# LED1710050926.net
KiCad netlist of a schematic drawn in Altium Designer
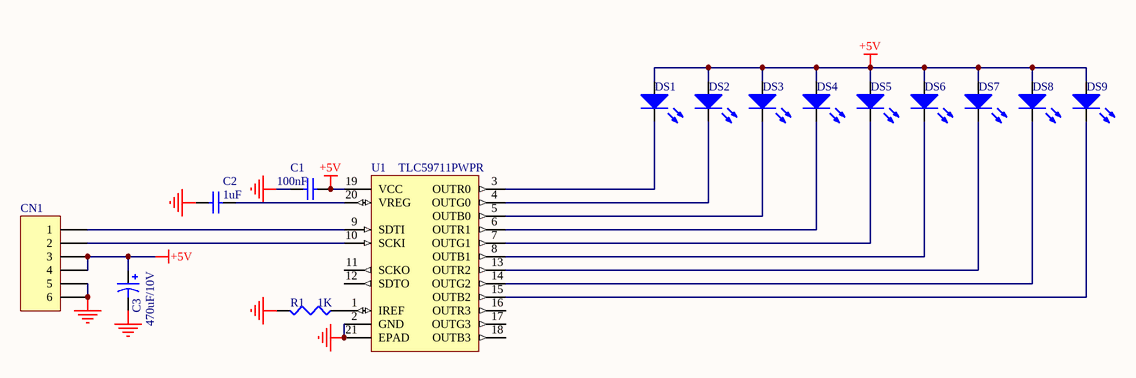
[diagram p0: LED1710050926.SchDoc]

(export (version "E")
  (design (tool "Eeschema 10.0.6"))
  (components
    (comp (ref "C1")
      (value "100nF")
      (footprint "C0603-3")
      (description "Capacitor")
      (fields (field (name "PUBLISHER") "Altium Limited"))
      (libsource (lib "Miscellaneous Devices") (part "Cap"))
    )
    (comp (ref "C2")
      (value "1uF")
      (footprint "C0603-3")
      (description "Capacitor")
      (fields (field (name "PUBLISHER") "Altium Limited"))
      (libsource (lib "Miscellaneous Devices") (part "Cap"))
    )
    (comp (ref "C3")
      (value "470uF/10V")
      (footprint "CASE-D_7343")
      (description "Polarized Capacitor (Radial)")
      (fields (field (name "PUBLISHER") "Altium Limited"))
      (libsource (lib "Miscellaneous Devices") (part "Cap Pol1"))
    )
    (comp (ref "CN1")
      (value "~")
      (footprint "FFC/SM1.0-2H6")
      (description "Header, 6-Pin")
      (fields (field (name "PUBLISHER") "Altium Limited"))
      (libsource (lib "Miscellaneous Connectors") (part "Header 6"))
    )
    (comp (ref "DS1")
      (value "~")
      (footprint "LED2-2.54-5C")
      (description "Typical INFRARED GaAs LED")
      (fields (field (name "PUBLISHER") "Altium Limited"))
      (libsource (lib "Sch1609122025") (part "LED0"))
    )
    (comp (ref "DS2")
      (value "~")
      (footprint "LED2-2.54-5C")
      (description "Typical INFRARED GaAs LED")
      (fields (field (name "PUBLISHER") "Altium Limited"))
      (libsource (lib "Sch1609122025") (part "LED0"))
    )
    (comp (ref "DS3")
      (value "~")
      (footprint "LED2-2.54-5C")
      (description "Typical INFRARED GaAs LED")
      (fields (field (name "PUBLISHER") "Altium Limited"))
      (libsource (lib "Sch1609122025") (part "LED0"))
    )
    (comp (ref "DS4")
      (value "~")
      (footprint "LED2-2.54-5C")
      (description "Typical INFRARED GaAs LED")
      (fields (field (name "PUBLISHER") "Altium Limited"))
      (libsource (lib "Sch1609122025") (part "LED0"))
    )
    (comp (ref "DS5")
      (value "~")
      (footprint "LED2-2.54-5C")
      (description "Typical INFRARED GaAs LED")
      (fields (field (name "PUBLISHER") "Altium Limited"))
      (libsource (lib "Sch1609122025") (part "LED0"))
    )
    (comp (ref "DS6")
      (value "~")
      (footprint "LED2-2.54-5C")
      (description "Typical INFRARED GaAs LED")
      (fields (field (name "PUBLISHER") "Altium Limited"))
      (libsource (lib "Sch1609122025") (part "LED0"))
    )
    (comp (ref "DS7")
      (value "~")
      (footprint "LED2-2.54-5C")
      (description "Typical INFRARED GaAs LED")
      (fields (field (name "PUBLISHER") "Altium Limited"))
      (libsource (lib "Sch1609122025") (part "LED0"))
    )
    (comp (ref "DS8")
      (value "~")
      (footprint "LED2-2.54-5C")
      (description "Typical INFRARED GaAs LED")
      (fields (field (name "PUBLISHER") "Altium Limited"))
      (libsource (lib "Sch1609122025") (part "LED0"))
    )
    (comp (ref "DS9")
      (value "~")
      (footprint "LED2-2.54-5C")
      (description "Typical INFRARED GaAs LED")
      (fields (field (name "PUBLISHER") "Altium Limited"))
      (libsource (lib "Sch1609122025") (part "LED0"))
    )
    (comp (ref "R1")
      (value "1K")
      (footprint "R0603-3")
      (description "Resistor")
      (fields (field (name "PUBLISHER") "Altium Limited"))
      (libsource (lib "Miscellaneous Devices") (part "Res3"))
    )
    (comp (ref "U1")
      (value "TLC59711PWPR")
      (footprint "HTSSOP20")
      (description "12-Channel,16-Bit,LED Driver with 3.3-V Linear Ragulator")
      (libsource (lib "Sch1705181056") (part "TLC59711"))
    )
  )
  (nets
    (net (code "1") (name "+5V") (class "Default")
      (node (ref "C1") (pin "1") (pinfunction "1_1") (pintype "passive"))
      (node (ref "C3") (pin "1") (pinfunction "1_1") (pintype "passive"))
      (node (ref "CN1") (pin "3") (pinfunction "3_3") (pintype "passive"))
      (node (ref "CN1") (pin "4") (pinfunction "4_4") (pintype "passive"))
      (node (ref "DS1") (pin "1") (pinfunction "A_1") (pintype "passive"))
      (node (ref "DS2") (pin "1") (pinfunction "A_1") (pintype "passive"))
      (node (ref "DS3") (pin "1") (pinfunction "A_1") (pintype "passive"))
      (node (ref "DS4") (pin "1") (pinfunction "A_1") (pintype "passive"))
      (node (ref "DS5") (pin "1") (pinfunction "A_1") (pintype "passive"))
      (node (ref "DS6") (pin "1") (pinfunction "A_1") (pintype "passive"))
      (node (ref "DS7") (pin "1") (pinfunction "A_1") (pintype "passive"))
      (node (ref "DS8") (pin "1") (pinfunction "A_1") (pintype "passive"))
      (node (ref "DS9") (pin "1") (pinfunction "A_1") (pintype "passive"))
      (node (ref "U1") (pin "19") (pinfunction "VCC_19") (pintype "power_in"))
    )
    (net (code "2") (name "GND") (class "Default")
      (node (ref "C1") (pin "2") (pinfunction "2_2") (pintype "passive"))
      (node (ref "C2") (pin "2") (pinfunction "2_2") (pintype "passive"))
      (node (ref "C3") (pin "2") (pinfunction "2_2") (pintype "passive"))
      (node (ref "CN1") (pin "5") (pinfunction "5_5") (pintype "passive"))
      (node (ref "CN1") (pin "6") (pinfunction "6_6") (pintype "passive"))
      (node (ref "R1") (pin "2") (pinfunction "2_2") (pintype "passive"))
      (node (ref "U1") (pin "2") (pinfunction "GND_2") (pintype "power_in"))
      (node (ref "U1") (pin "21") (pinfunction "EPAD_21") (pintype "passive"))
    )
    (net (code "3") (name "Net-(DS1-K)") (class "Default")
      (node (ref "DS1") (pin "2") (pinfunction "K_2") (pintype "passive"))
      (node (ref "U1") (pin "3") (pinfunction "OUTR0_3") (pintype "output"))
    )
    (net (code "4") (name "Net-(DS2-K)") (class "Default")
      (node (ref "DS2") (pin "2") (pinfunction "K_2") (pintype "passive"))
      (node (ref "U1") (pin "4") (pinfunction "OUTG0_4") (pintype "output"))
    )
    (net (code "5") (name "Net-(DS3-K)") (class "Default")
      (node (ref "DS3") (pin "2") (pinfunction "K_2") (pintype "passive"))
      (node (ref "U1") (pin "5") (pinfunction "OUTB0_5") (pintype "output"))
    )
    (net (code "6") (name "Net-(DS4-K)") (class "Default")
      (node (ref "DS4") (pin "2") (pinfunction "K_2") (pintype "passive"))
      (node (ref "U1") (pin "6") (pinfunction "OUTR1_6") (pintype "output"))
    )
    (net (code "7") (name "Net-(DS5-K)") (class "Default")
      (node (ref "DS5") (pin "2") (pinfunction "K_2") (pintype "passive"))
      (node (ref "U1") (pin "7") (pinfunction "OUTG1_7") (pintype "output"))
    )
    (net (code "8") (name "Net-(DS6-K)") (class "Default")
      (node (ref "DS6") (pin "2") (pinfunction "K_2") (pintype "passive"))
      (node (ref "U1") (pin "8") (pinfunction "OUTB1_8") (pintype "output"))
    )
    (net (code "9") (name "Net-(DS7-K)") (class "Default")
      (node (ref "DS7") (pin "2") (pinfunction "K_2") (pintype "passive"))
      (node (ref "U1") (pin "13") (pinfunction "OUTR2_13") (pintype "output"))
    )
    (net (code "10") (name "Net-(DS8-K)") (class "Default")
      (node (ref "DS8") (pin "2") (pinfunction "K_2") (pintype "passive"))
      (node (ref "U1") (pin "14") (pinfunction "OUTG2_14") (pintype "output"))
    )
    (net (code "11") (name "Net-(DS9-K)") (class "Default")
      (node (ref "DS9") (pin "2") (pinfunction "K_2") (pintype "passive"))
      (node (ref "U1") (pin "15") (pinfunction "OUTB2_15") (pintype "output"))
    )
    (net (code "12") (name "Net-(U1-IREF)") (class "Default")
      (node (ref "R1") (pin "1") (pinfunction "1_1") (pintype "passive"))
      (node (ref "U1") (pin "1") (pinfunction "IREF_1") (pintype "bidirectional"))
    )
    (net (code "13") (name "Net-(U1-SCKI)") (class "Default")
      (node (ref "CN1") (pin "2") (pinfunction "2_2") (pintype "passive"))
      (node (ref "U1") (pin "10") (pinfunction "SCKI_10") (pintype "input"))
    )
    (net (code "14") (name "Net-(U1-SDTI)") (class "Default")
      (node (ref "CN1") (pin "1") (pinfunction "1_1") (pintype "passive"))
      (node (ref "U1") (pin "9") (pinfunction "SDTI_9") (pintype "input"))
    )
    (net (code "15") (name "Net-(U1-VREG)") (class "Default")
      (node (ref "C2") (pin "1") (pinfunction "1_1") (pintype "passive"))
      (node (ref "U1") (pin "20") (pinfunction "VREG_20") (pintype "bidirectional"))
    )
    (net (code "16") (name "unconnected-(U1-OUTB3-Pad18)") (class "Default")
      (node (ref "U1") (pin "18") (pinfunction "OUTB3_18") (pintype "output"))
    )
    (net (code "17") (name "unconnected-(U1-OUTG3-Pad17)") (class "Default")
      (node (ref "U1") (pin "17") (pinfunction "OUTG3_17") (pintype "output"))
    )
    (net (code "18") (name "unconnected-(U1-OUTR3-Pad16)") (class "Default")
      (node (ref "U1") (pin "16") (pinfunction "OUTR3_16") (pintype "output"))
    )
    (net (code "19") (name "unconnected-(U1-SCKO-Pad11)") (class "Default")
      (node (ref "U1") (pin "11") (pinfunction "SCKO_11") (pintype "output"))
    )
    (net (code "20") (name "unconnected-(U1-SDTO-Pad12)") (class "Default")
      (node (ref "U1") (pin "12") (pinfunction "SDTO_12") (pintype "output"))
    )
  )
)
